# Torque_Signal_Conditioning.net
KiCad netlist of a schematic drawn in Altium Designer
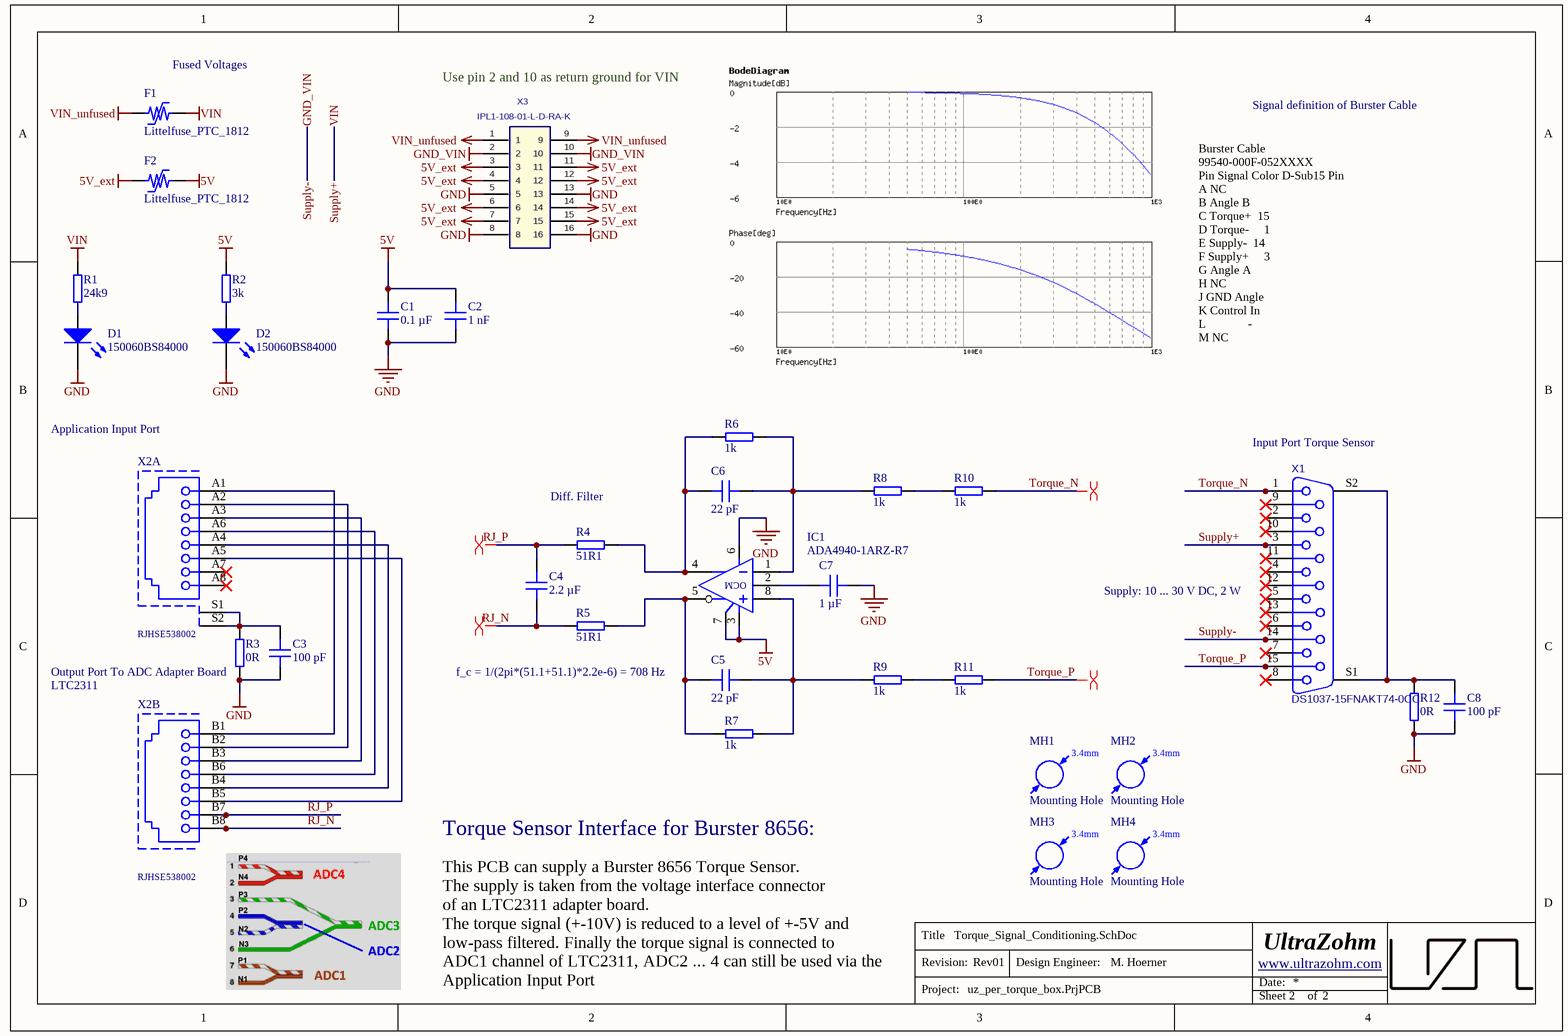
[diagram p0: Torque_Signal_Conditioning.SchDoc]

(export (version "E")
  (design (tool "Eeschema 10.0.6"))
  (components
    (comp (ref "C1")
      (value "0.1 µF")
      (footprint "C_0603")
      (description "Capacitor 0603, 50 VDC, 0.1 µF, X7R")
      (fields
        (field (name "MANUFACTURER PART NUMBER") "C0603X104K5RAC7411")
        (field (name "MANUFACTURER") "KEMET")
        (field (name "CREATED FROM") "MGremer")
      )
      (libsource (lib "user") (part "Capacitor"))
    )
    (comp (ref "C2")
      (value "1 nF")
      (footprint "C_0603")
      (description "Capacitor 0603, 50 VDC, 1 nF, NP0")
      (fields
        (field (name "MANUFACTURER PART NUMBER") "CC0603JRNPO9BN102")
        (field (name "MANUFACTURER") "YAGEO")
        (field (name "CREATED FROM") "AGeiger")
      )
      (libsource (lib "user") (part "Capacitor"))
    )
    (comp (ref "C3")
      (value "100 pF")
      (footprint "C_1206")
      (description "Capacitor 1206, 1 kVDC, 100 pF, C0G")
      (fields
        (field (name "MANUFACTURER PART NUMBER") "885342008009")
        (field (name "MANUFACTURER") "Wuerth Elektronik")
        (field (name "CREATED FROM") "MGremer")
      )
      (libsource (lib "user") (part "Capacitor"))
    )
    (comp (ref "C4")
      (value "2.2 µF")
      (footprint "C_0805")
      (description "Capacitor 0805, 16 VDC, 2.2 µF, X7R")
      (fields
        (field (name "MANUFACTURER PART NUMBER") "C0805X225J4RECAUTO")
        (field (name "MANUFACTURER") "KEMET")
        (field (name "CREATED FROM") "MGremer")
      )
      (libsource (lib "user") (part "Capacitor"))
    )
    (comp (ref "C5")
      (value "22 pF")
      (footprint "C_0603")
      (description "Capacitor 0603, 50 VDC, 22 pF, X7R")
      (fields
        (field (name "MANUFACTURER PART NUMBER") "C0603C220J5RACTU")
        (field (name "MANUFACTURER") "KEMET")
        (field (name "CREATED FROM") "MGremer")
      )
      (libsource (lib "user") (part "Capacitor"))
    )
    (comp (ref "C6")
      (value "22 pF")
      (footprint "C_0603")
      (description "Capacitor 0603, 50 VDC, 22 pF, X7R")
      (fields
        (field (name "MANUFACTURER PART NUMBER") "C0603C220J5RACTU")
        (field (name "MANUFACTURER") "KEMET")
        (field (name "CREATED FROM") "MGremer")
      )
      (libsource (lib "user") (part "Capacitor"))
    )
    (comp (ref "C7")
      (value "1 µF")
      (footprint "C_0603")
      (description "50V 1uF X7R ±10% 0603 Multilayer Ceramic Capacitors MLCC - SMD/SMT ROHS")
      (fields
        (field (name "MANUFACTURER PART NUMBER") "UMK107AB7105KA-T")
        (field (name "MANUFACTURER") "Taiyo Yuden")
        (field (name "CREATED FROM") "NDiringer")
      )
      (libsource (lib "user") (part "Capacitor"))
    )
    (comp (ref "C8")
      (value "100 pF")
      (footprint "C_1206")
      (description "Capacitor 1206, 1 kVDC, 100 pF, C0G")
      (fields
        (field (name "MANUFACTURER PART NUMBER") "885342008009")
        (field (name "MANUFACTURER") "Wuerth Elektronik")
        (field (name "CREATED FROM") "MGremer")
      )
      (libsource (lib "user") (part "Capacitor"))
    )
    (comp (ref "D1")
      (value "150060BS84000")
      (footprint "WL-SMCW_0603")
      (description "WL-SMCW SMD Mono-color Chip LED Waterclear Blue")
      (fields (field (name "MANUFACTURER") "Wuerth Elektronik") (field (name "CREATED FROM") "MGremer"))
      (libsource (lib "user") (part "LED_Blue"))
    )
    (comp (ref "D2")
      (value "150060BS84000")
      (footprint "WL-SMCW_0603")
      (description "WL-SMCW SMD Mono-color Chip LED Waterclear Blue")
      (fields
        (field (name "MANUFACTURER") "Wuerth Elektronik")
        (field (name "LCSC PART NUMBER") "C5197644")
        (field (name "CREATED FROM") "MGremer")
      )
      (libsource (lib "user") (part "LED_Blue"))
    )
    (comp (ref "F1")
      (value "Littelfuse_PTC_1812")
      (footprint "1812_PTC_Polyfuse_Littelfuse")
      (description "POLYSWITCH RESETTABLE DEVICES")
      (fields
        (field (name "MPN") "miniASMDC110F/24")
        (field (name "MF") "Littelfuse")
        (field (name "CREATED") "2019_02_10_AGeiger")
        (field (name "CREATED FROM") "MHlatky")
      )
      (libsource (lib "user") (part "Littelfuse_PTC_1812"))
    )
    (comp (ref "F2")
      (value "Littelfuse_PTC_1812")
      (footprint "1812_PTC_Polyfuse_Littelfuse")
      (description "POLYSWITCH RESETTABLE DEVICES")
      (fields
        (field (name "MPN") "miniASMDC110F/24")
        (field (name "MF") "Littelfuse")
        (field (name "CREATED") "2019_02_10_AGeiger")
        (field (name "CREATED FROM") "MHlatky")
      )
      (libsource (lib "user") (part "Littelfuse_PTC_1812"))
    )
    (comp (ref "IC1")
      (value "ADA4940-1ARZ-R7")
      (footprint "SOIC-8-N")
      (description "Differential ADC Driver")
      (fields (field (name "MANUFACTURER") "Analog Devices") (field (name "CREATED FROM") "MGremer"))
      (libsource (lib "user") (part "ADA4940-1ARZ"))
    )
    (comp (ref "MH1")
      (value "Mounting Hole")
      (footprint "MH_3.4")
      (fields (field (name "CREATED FROM") "MHlatky"))
      (libsource (lib "user") (part "Mounting Hole"))
    )
    (comp (ref "MH2")
      (value "Mounting Hole")
      (footprint "MH_3.4")
      (fields (field (name "CREATED FROM") "MHlatky"))
      (libsource (lib "user") (part "Mounting Hole"))
    )
    (comp (ref "MH3")
      (value "Mounting Hole")
      (footprint "MH_3.4")
      (fields (field (name "CREATED FROM") "MHlatky"))
      (libsource (lib "user") (part "Mounting Hole"))
    )
    (comp (ref "MH4")
      (value "Mounting Hole")
      (footprint "MH_3.4")
      (fields (field (name "CREATED FROM") "MHlatky"))
      (libsource (lib "user") (part "Mounting Hole"))
    )
    (comp (ref "R1")
      (value "24k9")
      (footprint "RES 0603_1608")
      (description "SMD resistor 1%")
      (fields
        (field (name "MANUFACTURER PART NUMBER") "CRCW060324K9FKEA")
        (field (name "MANUFACTURER") "Vishay")
        (field (name "CREATED FROM") "MGremer")
      )
      (libsource (lib "user") (part "Resistor"))
    )
    (comp (ref "R2")
      (value "3k")
      (footprint "RES 0603_1608")
      (description "SMD resistor E24 series")
      (fields
        (field (name "MANUFACTURER PART NUMBER") "RK73B1JTTD302J")
        (field (name "MANUFACTURER") "KOA Speer")
        (field (name "CREATED FROM") "MGremer")
      )
      (libsource (lib "user") (part "Resistor"))
    )
    (comp (ref "R3")
      (value "0R")
      (footprint "RES 1206_3216")
      (description "250mW Thick Film Resistors ±800ppm/℃ ±1% 0Ω 1206 Chip Resistor - Surface Mount ROHS")
      (fields
        (field (name "MANUFACTURER PART NUMBER") "1206W4F0000T5E")
        (field (name "MANUFACTURER") "UNI-ROYAL")
        (field (name "CREATED FROM") "AGeiger")
      )
      (libsource (lib "user") (part "Resistor"))
    )
    (comp (ref "R4")
      (value "51R1")
      (footprint "RES 0603_1608")
      (description "SMD resistor 0.1%")
      (fields
        (field (name "MANUFACTURER PART NUMBER") "RT0603BRD0751R1L")
        (field (name "MANUFACTURER") "YAGEO")
        (field (name "CREATED FROM") "DHufnagel")
      )
      (libsource (lib "user") (part "Resistor"))
    )
    (comp (ref "R5")
      (value "51R1")
      (footprint "RES 0603_1608")
      (description "SMD resistor 0.1%")
      (fields
        (field (name "MANUFACTURER PART NUMBER") "RT0603BRD0751R1L")
        (field (name "MANUFACTURER") "YAGEO")
        (field (name "CREATED FROM") "DHufnagel")
      )
      (libsource (lib "user") (part "Resistor"))
    )
    (comp (ref "R6")
      (value "1k")
      (footprint "RES 0603_1608")
      (description "SMD resistor 0.1%")
      (fields
        (field (name "MANUFACTURER PART NUMBER") "PCF-W0603LF-03-1001-B-P-LT")
        (field (name "MANUFACTURER") "IRC / TT Electronics")
        (field (name "CREATED FROM") "MGremer")
      )
      (libsource (lib "user") (part "Resistor"))
    )
    (comp (ref "R7")
      (value "1k")
      (footprint "RES 0603_1608")
      (description "SMD resistor 0.1%")
      (fields
        (field (name "MANUFACTURER PART NUMBER") "PCF-W0603LF-03-1001-B-P-LT")
        (field (name "MANUFACTURER") "IRC / TT Electronics")
        (field (name "CREATED FROM") "MGremer")
      )
      (libsource (lib "user") (part "Resistor"))
    )
    (comp (ref "R8")
      (value "1k")
      (footprint "RES 0603_1608")
      (description "SMD resistor 0.1%")
      (fields
        (field (name "MANUFACTURER PART NUMBER") "PCF-W0603LF-03-1001-B-P-LT")
        (field (name "MANUFACTURER") "IRC / TT Electronics")
        (field (name "CREATED FROM") "MGremer")
      )
      (libsource (lib "user") (part "Resistor"))
    )
    (comp (ref "R9")
      (value "1k")
      (footprint "RES 0603_1608")
      (description "SMD resistor 0.1%")
      (fields
        (field (name "MANUFACTURER PART NUMBER") "PCF-W0603LF-03-1001-B-P-LT")
        (field (name "MANUFACTURER") "IRC / TT Electronics")
        (field (name "CREATED FROM") "MGremer")
      )
      (libsource (lib "user") (part "Resistor"))
    )
    (comp (ref "R10")
      (value "1k")
      (footprint "RES 0603_1608")
      (description "SMD resistor 0.1%")
      (fields
        (field (name "MANUFACTURER PART NUMBER") "PCF-W0603LF-03-1001-B-P-LT")
        (field (name "MANUFACTURER") "IRC / TT Electronics")
        (field (name "CREATED FROM") "MGremer")
      )
      (libsource (lib "user") (part "Resistor"))
    )
    (comp (ref "R11")
      (value "1k")
      (footprint "RES 0603_1608")
      (description "SMD resistor 0.1%")
      (fields
        (field (name "MANUFACTURER PART NUMBER") "PCF-W0603LF-03-1001-B-P-LT")
        (field (name "MANUFACTURER") "IRC / TT Electronics")
        (field (name "CREATED FROM") "MGremer")
      )
      (libsource (lib "user") (part "Resistor"))
    )
    (comp (ref "R12")
      (value "0R")
      (footprint "RES 1206_3216")
      (description "250mW Thick Film Resistors ±800ppm/℃ ±1% 0Ω 1206 Chip Resistor - Surface Mount ROHS")
      (fields
        (field (name "MANUFACTURER PART NUMBER") "1206W4F0000T5E")
        (field (name "MANUFACTURER") "UNI-ROYAL")
        (field (name "CREATED FROM") "AGeiger")
      )
      (libsource (lib "user") (part "Resistor"))
    )
    (comp (ref "X1")
      (value "DS1037-15FNAKT74-0CC")
      (footprint "PCB - MISC - DSUB15")
      (description "15 Female D-Sub Shrouded 2 3A -40℃~+85℃ Plugin D-Sub/DVI/HDMI Connectors ROHS")
      (fields
        (field (name "BOM_SUPPLIER PART") "C2846090")
        (field (name "BOM_MANUFACTURER PART") "SUB-DRBF-607A-002")
        (field (name "CONTRIBUTOR") "LCSC")
        (field (name "CREATED FROM") "FRosner")
      )
      (libsource (lib "user") (part "SUB-DRBF-607A-002"))
    )
    (comp (ref "X2")
      (value "RJHSE538002")
      (footprint "RJHSE-5380-02")
      (description "CAT5, RJ45 Connector, 1x2")
      (fields (field (name "MANUFACTURER") "Amphenol") (field (name "CREATED FROM") "MGremer"))
      (libsource (lib "user") (part "RJHSE-5380-02"))
    )
    (comp (ref "X3")
      (value "IPL1-108-01-L-D-RA-K")
      (footprint "IPL1-108-01-L-D-RA-K")
      (description "2.54 mm Double Row Termin Assembly (right angle)")
      (fields (field (name "MANUFACTURER") "SAMTEC") (field (name "CREATED FROM") "MGremer"))
      (libsource (lib "user") (part "IPL1-108-XX-X-D-X"))
    )
  )
  (nets
    (net (code "1") (name "/RJ_N") (class "Default")
      (node (ref "C4") (pin "1") (pinfunction "1_1") (pintype "passive"))
      (node (ref "R5") (pin "1") (pinfunction "1_1") (pintype "passive"))
      (node (ref "X2") (pin "B8") (pinfunction "B8_B8") (pintype "passive"))
    )
    (net (code "2") (name "/RJ_P") (class "Default")
      (node (ref "C4") (pin "2") (pinfunction "2_2") (pintype "passive"))
      (node (ref "R4") (pin "1") (pinfunction "1_1") (pintype "passive"))
      (node (ref "X2") (pin "B7") (pinfunction "B7_B7") (pintype "passive"))
    )
    (net (code "3") (name "/Torque_N") (class "Default")
      (node (ref "R10") (pin "2") (pinfunction "2_2") (pintype "passive"))
      (node (ref "X1") (pin "1") (pinfunction "1_1") (pintype "passive"))
    )
    (net (code "4") (name "/Torque_P") (class "Default")
      (node (ref "R11") (pin "2") (pinfunction "2_2") (pintype "passive"))
      (node (ref "X1") (pin "15") (pinfunction "15_15") (pintype "passive"))
    )
    (net (code "5") (name "5V") (class "Default")
      (node (ref "C1") (pin "2") (pinfunction "2_2") (pintype "passive"))
      (node (ref "C2") (pin "2") (pinfunction "2_2") (pintype "passive"))
      (node (ref "F2") (pin "2") (pinfunction "2_2") (pintype "passive"))
      (node (ref "IC1") (pin "3") (pinfunction "V+_3") (pintype "passive"))
      (node (ref "IC1") (pin "7") (pinfunction "EN_7") (pintype "passive"))
      (node (ref "R2") (pin "2") (pinfunction "2_2") (pintype "passive"))
    )
    (net (code "6") (name "5V_ext") (class "Default")
      (node (ref "F2") (pin "1") (pinfunction "1_1") (pintype "passive"))
      (node (ref "X3") (pin "11") (pinfunction "11_11") (pintype "passive"))
      (node (ref "X3") (pin "12") (pinfunction "12_12") (pintype "passive"))
      (node (ref "X3") (pin "14") (pinfunction "14_14") (pintype "passive"))
      (node (ref "X3") (pin "15") (pinfunction "15_15") (pintype "passive"))
      (node (ref "X3") (pin "3") (pinfunction "3_3") (pintype "passive"))
      (node (ref "X3") (pin "4") (pinfunction "4_4") (pintype "passive"))
      (node (ref "X3") (pin "6") (pinfunction "6_6") (pintype "passive"))
      (node (ref "X3") (pin "7") (pinfunction "7_7") (pintype "passive"))
    )
    (net (code "7") (name "GND") (class "Default")
      (node (ref "C1") (pin "1") (pinfunction "1_1") (pintype "passive"))
      (node (ref "C2") (pin "1") (pinfunction "1_1") (pintype "passive"))
      (node (ref "C3") (pin "1") (pinfunction "1_1") (pintype "passive"))
      (node (ref "C7") (pin "1") (pinfunction "1_1") (pintype "passive"))
      (node (ref "C8") (pin "1") (pinfunction "1_1") (pintype "passive"))
      (node (ref "D1") (pin "1") (pinfunction "K_1") (pintype "passive"))
      (node (ref "D2") (pin "1") (pinfunction "K_1") (pintype "passive"))
      (node (ref "IC1") (pin "6") (pinfunction "V-_6") (pintype "passive"))
      (node (ref "R12") (pin "1") (pinfunction "1_1") (pintype "passive"))
      (node (ref "R3") (pin "1") (pinfunction "1_1") (pintype "passive"))
      (node (ref "X3") (pin "13") (pinfunction "13_13") (pintype "passive"))
      (node (ref "X3") (pin "16") (pinfunction "16_16") (pintype "passive"))
      (node (ref "X3") (pin "5") (pinfunction "5_5") (pintype "passive"))
      (node (ref "X3") (pin "8") (pinfunction "8_8") (pintype "passive"))
    )
    (net (code "8") (name "GND_VIN") (class "Default")
      (node (ref "X1") (pin "14") (pinfunction "14_14") (pintype "passive"))
      (node (ref "X3") (pin "10") (pinfunction "10_10") (pintype "passive"))
      (node (ref "X3") (pin "2") (pinfunction "2_2") (pintype "passive"))
    )
    (net (code "9") (name "Net-(C3-Pad2)") (class "Default")
      (node (ref "C3") (pin "2") (pinfunction "2_2") (pintype "passive"))
      (node (ref "R3") (pin "2") (pinfunction "2_2") (pintype "passive"))
      (node (ref "X2") (pin "S1") (pinfunction "S1_S1") (pintype "passive"))
      (node (ref "X2") (pin "S2") (pinfunction "S2_S2") (pintype "passive"))
    )
    (net (code "10") (name "Net-(C5-Pad2)") (class "Default")
      (node (ref "C5") (pin "2") (pinfunction "2_2") (pintype "passive"))
      (node (ref "IC1") (pin "5") (pinfunction "Out_5") (pintype "passive"))
      (node (ref "R5") (pin "2") (pinfunction "2_2") (pintype "passive"))
      (node (ref "R7") (pin "1") (pinfunction "1_1") (pintype "passive"))
    )
    (net (code "11") (name "Net-(C6-Pad2)") (class "Default")
      (node (ref "C6") (pin "2") (pinfunction "2_2") (pintype "passive"))
      (node (ref "IC1") (pin "4") (pinfunction "Out_4") (pintype "passive"))
      (node (ref "R4") (pin "2") (pinfunction "2_2") (pintype "passive"))
      (node (ref "R6") (pin "1") (pinfunction "1_1") (pintype "passive"))
    )
    (net (code "12") (name "Net-(D1-A)") (class "Default")
      (node (ref "D1") (pin "2") (pinfunction "A_2") (pintype "passive"))
      (node (ref "R1") (pin "1") (pinfunction "1_1") (pintype "passive"))
    )
    (net (code "13") (name "Net-(D2-A)") (class "Default")
      (node (ref "D2") (pin "2") (pinfunction "A_2") (pintype "passive"))
      (node (ref "R2") (pin "1") (pinfunction "1_1") (pintype "passive"))
    )
    (net (code "14") (name "Net-(IC1-+)") (class "Default")
      (node (ref "C5") (pin "1") (pinfunction "1_1") (pintype "passive"))
      (node (ref "IC1") (pin "8") (pinfunction "+_8") (pintype "passive"))
      (node (ref "R7") (pin "2") (pinfunction "2_2") (pintype "passive"))
      (node (ref "R9") (pin "1") (pinfunction "1_1") (pintype "passive"))
    )
    (net (code "15") (name "Net-(IC1--)") (class "Default")
      (node (ref "C6") (pin "1") (pinfunction "1_1") (pintype "passive"))
      (node (ref "IC1") (pin "1") (pinfunction "-_1") (pintype "passive"))
      (node (ref "R6") (pin "2") (pinfunction "2_2") (pintype "passive"))
      (node (ref "R8") (pin "1") (pinfunction "1_1") (pintype "passive"))
    )
    (net (code "16") (name "Net-(IC1-OCM)") (class "Default")
      (node (ref "C7") (pin "2") (pinfunction "2_2") (pintype "passive"))
      (node (ref "IC1") (pin "2") (pinfunction "OCM_2") (pintype "passive"))
    )
    (net (code "17") (name "Net-(R10-Pad1)") (class "Default")
      (node (ref "R10") (pin "1") (pinfunction "1_1") (pintype "passive"))
      (node (ref "R8") (pin "2") (pinfunction "2_2") (pintype "passive"))
    )
    (net (code "18") (name "Net-(R11-Pad1)") (class "Default")
      (node (ref "R11") (pin "1") (pinfunction "1_1") (pintype "passive"))
      (node (ref "R9") (pin "2") (pinfunction "2_2") (pintype "passive"))
    )
    (net (code "19") (name "Net-(X1-MH1)") (class "Default")
      (node (ref "C8") (pin "2") (pinfunction "2_2") (pintype "passive"))
      (node (ref "R12") (pin "2") (pinfunction "2_2") (pintype "passive"))
      (node (ref "X1") (pin "S1") (pinfunction "MH1_S1") (pintype "passive"))
      (node (ref "X1") (pin "S2") (pinfunction "MH2_S2") (pintype "passive"))
    )
    (net (code "20") (name "Net-(X2-PadA1)") (class "Default")
      (node (ref "X2") (pin "A1") (pinfunction "A1_A1") (pintype "passive"))
      (node (ref "X2") (pin "B1") (pinfunction "B1_B1") (pintype "passive"))
    )
    (net (code "21") (name "Net-(X2-PadA2)") (class "Default")
      (node (ref "X2") (pin "A2") (pinfunction "A2_A2") (pintype "passive"))
      (node (ref "X2") (pin "B2") (pinfunction "B2_B2") (pintype "passive"))
    )
    (net (code "22") (name "Net-(X2-PadA3)") (class "Default")
      (node (ref "X2") (pin "A3") (pinfunction "A3_A3") (pintype "passive"))
      (node (ref "X2") (pin "B3") (pinfunction "B3_B3") (pintype "passive"))
    )
    (net (code "23") (name "Net-(X2-PadA4)") (class "Default")
      (node (ref "X2") (pin "A4") (pinfunction "A4_A4") (pintype "passive"))
      (node (ref "X2") (pin "B4") (pinfunction "B4_B4") (pintype "passive"))
    )
    (net (code "24") (name "Net-(X2-PadA5)") (class "Default")
      (node (ref "X2") (pin "A5") (pinfunction "A5_A5") (pintype "passive"))
      (node (ref "X2") (pin "B5") (pinfunction "B5_B5") (pintype "passive"))
    )
    (net (code "25") (name "Net-(X2-PadA6)") (class "Default")
      (node (ref "X2") (pin "A6") (pinfunction "A6_A6") (pintype "passive"))
      (node (ref "X2") (pin "B6") (pinfunction "B6_B6") (pintype "passive"))
    )
    (net (code "26") (name "VIN") (class "Default")
      (node (ref "F1") (pin "2") (pinfunction "2_2") (pintype "passive"))
      (node (ref "R1") (pin "2") (pinfunction "2_2") (pintype "passive"))
      (node (ref "X1") (pin "3") (pinfunction "3_3") (pintype "passive"))
    )
    (net (code "27") (name "VIN_unfused") (class "Default")
      (node (ref "F1") (pin "1") (pinfunction "1_1") (pintype "passive"))
      (node (ref "X3") (pin "1") (pinfunction "1_1") (pintype "passive"))
      (node (ref "X3") (pin "9") (pinfunction "9_9") (pintype "passive"))
    )
    (net (code "28") (name "unconnected-(X1-Pad2)") (class "Default")
      (node (ref "X1") (pin "2") (pinfunction "2_2") (pintype "passive+no_connect"))
    )
    (net (code "29") (name "unconnected-(X1-Pad4)") (class "Default")
      (node (ref "X1") (pin "4") (pinfunction "4_4") (pintype "passive+no_connect"))
    )
    (net (code "30") (name "unconnected-(X1-Pad5)") (class "Default")
      (node (ref "X1") (pin "5") (pinfunction "5_5") (pintype "passive+no_connect"))
    )
    (net (code "31") (name "unconnected-(X1-Pad6)") (class "Default")
      (node (ref "X1") (pin "6") (pinfunction "6_6") (pintype "passive+no_connect"))
    )
    (net (code "32") (name "unconnected-(X1-Pad7)") (class "Default")
      (node (ref "X1") (pin "7") (pinfunction "7_7") (pintype "passive+no_connect"))
    )
    (net (code "33") (name "unconnected-(X1-Pad8)") (class "Default")
      (node (ref "X1") (pin "8") (pinfunction "8_8") (pintype "passive+no_connect"))
    )
    (net (code "34") (name "unconnected-(X1-Pad9)") (class "Default")
      (node (ref "X1") (pin "9") (pinfunction "9_9") (pintype "passive+no_connect"))
    )
    (net (code "35") (name "unconnected-(X1-Pad10)") (class "Default")
      (node (ref "X1") (pin "10") (pinfunction "10_10") (pintype "passive+no_connect"))
    )
    (net (code "36") (name "unconnected-(X1-Pad11)") (class "Default")
      (node (ref "X1") (pin "11") (pinfunction "11_11") (pintype "passive+no_connect"))
    )
    (net (code "37") (name "unconnected-(X1-Pad12)") (class "Default")
      (node (ref "X1") (pin "12") (pinfunction "12_12") (pintype "passive+no_connect"))
    )
    (net (code "38") (name "unconnected-(X1-Pad13)") (class "Default")
      (node (ref "X1") (pin "13") (pinfunction "13_13") (pintype "passive+no_connect"))
    )
    (net (code "39") (name "unconnected-(X2-PadA7)") (class "Default")
      (node (ref "X2") (pin "A7") (pinfunction "A7_A7") (pintype "passive+no_connect"))
    )
    (net (code "40") (name "unconnected-(X2-PadA8)") (class "Default")
      (node (ref "X2") (pin "A8") (pinfunction "A8_A8") (pintype "passive+no_connect"))
    )
  )
)
